# Pill_Minder_shield.net
KiCad netlist of a schematic drawn in EAGLE
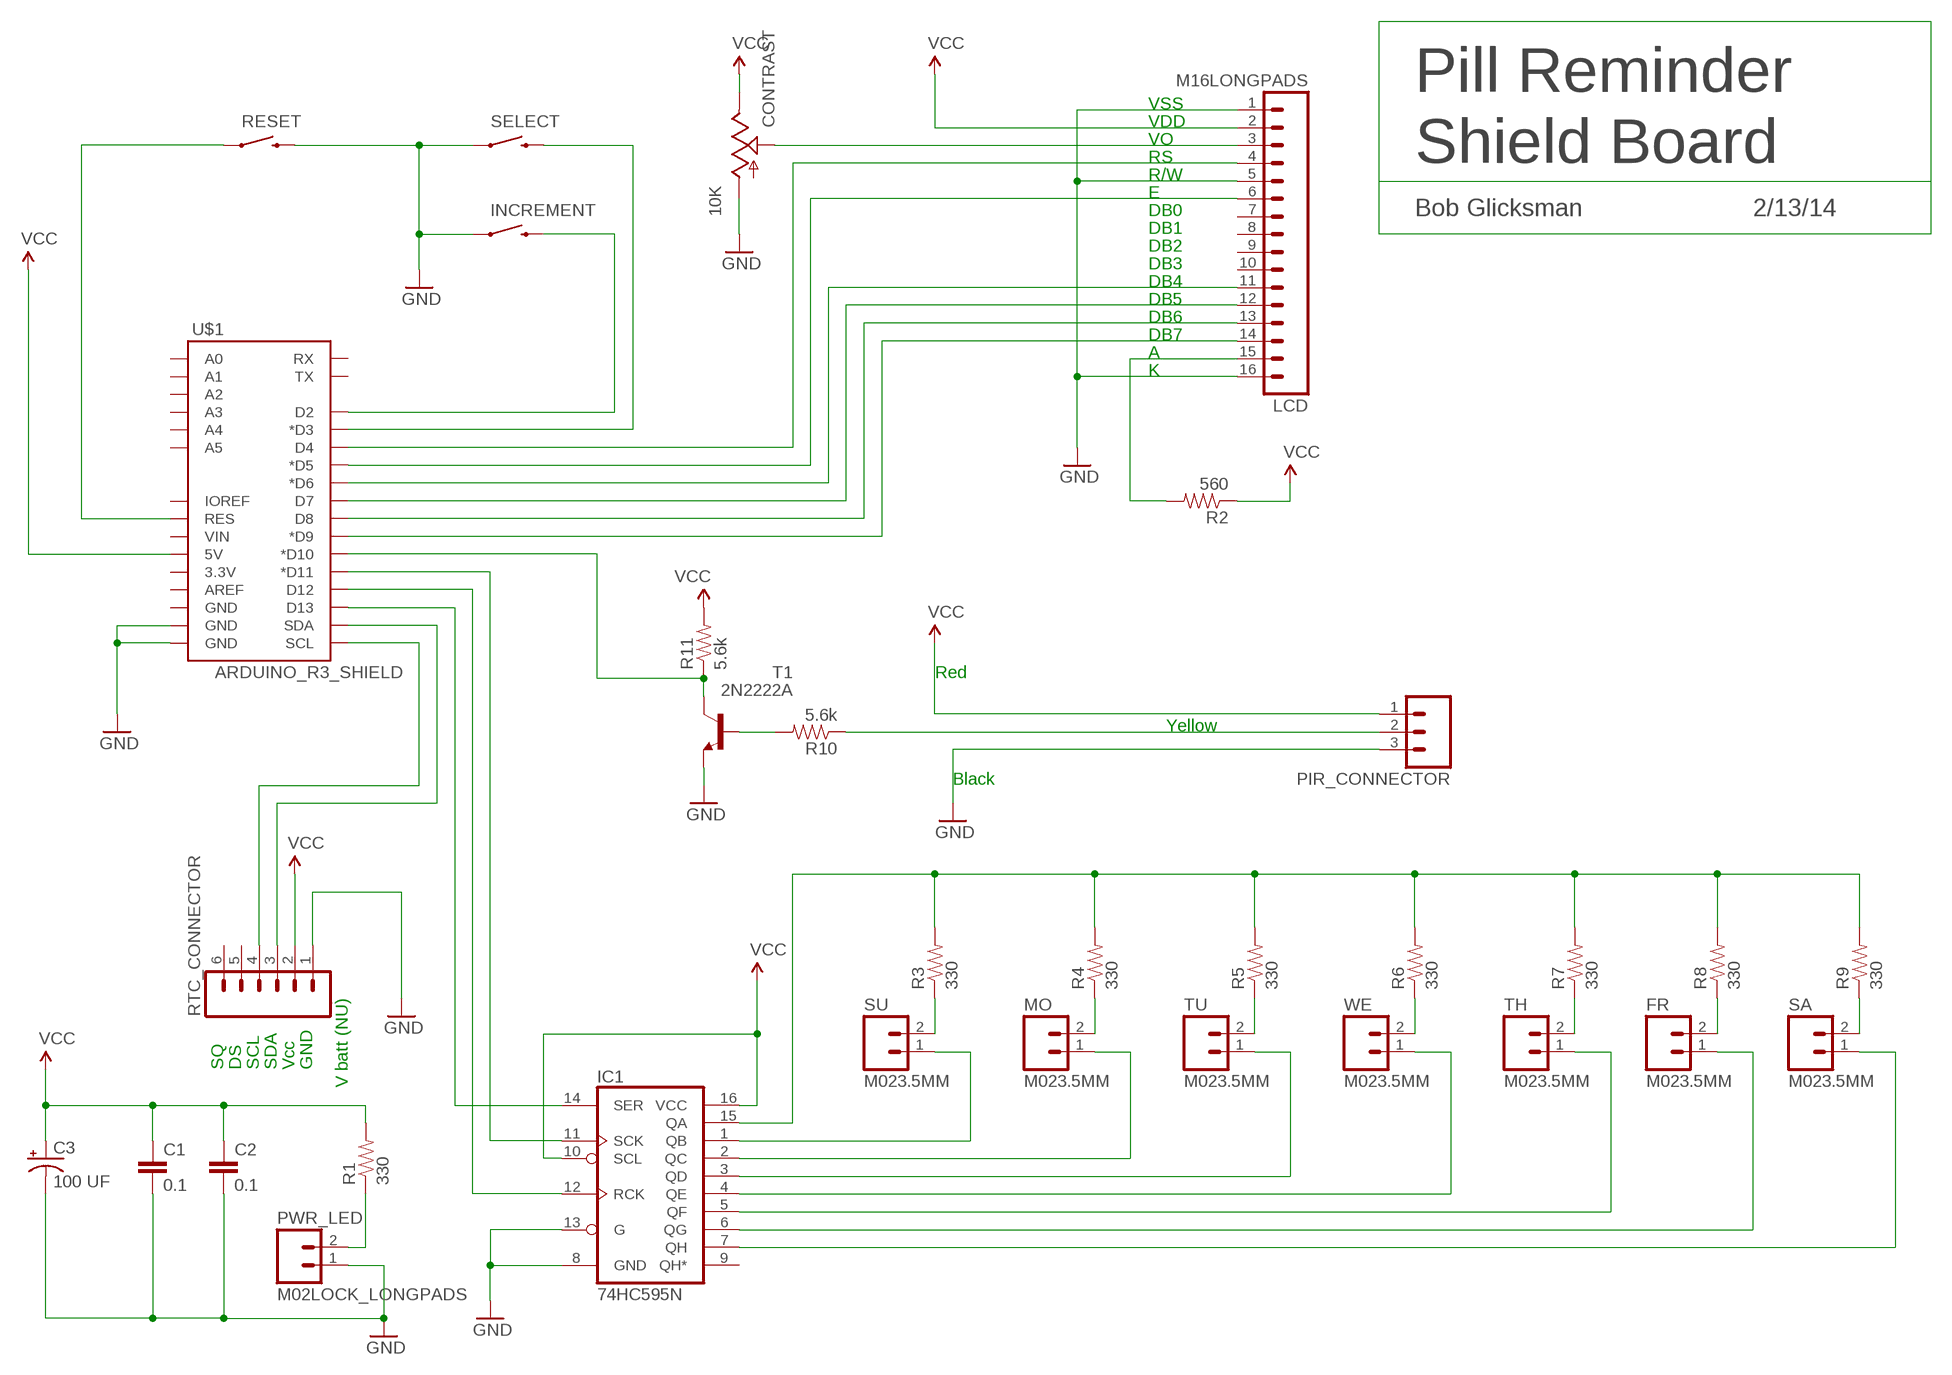
[diagram p0: schematic, sheet 1]

(export (version "E")
  (design (tool "Eeschema 10.0.6"))
  (components
    (comp (ref "C1")
      (value "0.1")
      (footprint "eagle-import:CAP-PTH-SMALL2")
      (libsource (lib "eagle-import") (part "CAPPTH2"))
    )
    (comp (ref "C2")
      (value "0.1")
      (footprint "eagle-import:CAP-PTH-SMALL2")
      (libsource (lib "eagle-import") (part "CAPPTH2"))
    )
    (comp (ref "C3")
      (value "100 UF")
      (footprint "eagle-import:CPOL-RADIAL-100UF-25V")
      (libsource (lib "eagle-import") (part "CAP_POLPTH1"))
    )
    (comp (ref "CONTRAST")
      (value "10K")
      (footprint "eagle-import:TRIM_POT")
      (libsource (lib "eagle-import") (part "POTTRIM"))
    )
    (comp (ref "FR")
      (value "M023.5MM")
      (footprint "eagle-import:SCREWTERMINAL-3.5MM-2")
      (libsource (lib "eagle-import") (part "M023.5MM"))
    )
    (comp (ref "IC1")
      (value "74HC595N")
      (footprint "eagle-import:DIL16")
      (libsource (lib "eagle-import") (part "74595NLS"))
    )
    (comp (ref "INCREMENT")
      (value "SWITCH-MOMENTARY-2PTH")
      (footprint "eagle-import:TACTILE-PTH")
      (libsource (lib "eagle-import") (part "SWITCH-MOMENTARY-2PTH"))
    )
    (comp (ref "LCD")
      (value "M16LONGPADS")
      (footprint "eagle-import:1X16_LONGPADS")
      (libsource (lib "eagle-import") (part "M16LONGPADS"))
    )
    (comp (ref "MO")
      (value "M023.5MM")
      (footprint "eagle-import:SCREWTERMINAL-3.5MM-2")
      (libsource (lib "eagle-import") (part "M023.5MM"))
    )
    (comp (ref "PIR_CONNECTOR")
      (value "M03LONGPADS")
      (footprint "eagle-import:1X03_LONGPADS")
      (libsource (lib "eagle-import") (part "M03LONGPADS"))
    )
    (comp (ref "PWR_LED")
      (value "M02LOCK_LONGPADS")
      (footprint "eagle-import:1X02_LOCK_LONGPADS")
      (libsource (lib "eagle-import") (part "M02LOCK_LONGPADS"))
    )
    (comp (ref "R1")
      (value "330")
      (footprint "eagle-import:AXIAL-0.4")
      (libsource (lib "eagle-import") (part "RESISTORPTH-1/4W"))
    )
    (comp (ref "R2")
      (value "560")
      (footprint "eagle-import:AXIAL-0.4")
      (libsource (lib "eagle-import") (part "RESISTORPTH-1/4W"))
    )
    (comp (ref "R3")
      (value "330")
      (footprint "eagle-import:AXIAL-0.4")
      (libsource (lib "eagle-import") (part "RESISTORPTH-1/4W"))
    )
    (comp (ref "R4")
      (value "330")
      (footprint "eagle-import:AXIAL-0.4")
      (libsource (lib "eagle-import") (part "RESISTORPTH-1/4W"))
    )
    (comp (ref "R5")
      (value "330")
      (footprint "eagle-import:AXIAL-0.4")
      (libsource (lib "eagle-import") (part "RESISTORPTH-1/4W"))
    )
    (comp (ref "R6")
      (value "330")
      (footprint "eagle-import:AXIAL-0.4")
      (libsource (lib "eagle-import") (part "RESISTORPTH-1/4W"))
    )
    (comp (ref "R7")
      (value "330")
      (footprint "eagle-import:AXIAL-0.4")
      (libsource (lib "eagle-import") (part "RESISTORPTH-1/4W"))
    )
    (comp (ref "R8")
      (value "330")
      (footprint "eagle-import:AXIAL-0.4")
      (libsource (lib "eagle-import") (part "RESISTORPTH-1/4W"))
    )
    (comp (ref "R9")
      (value "330")
      (footprint "eagle-import:AXIAL-0.4")
      (libsource (lib "eagle-import") (part "RESISTORPTH-1/4W"))
    )
    (comp (ref "R10")
      (value "5.6k")
      (footprint "eagle-import:AXIAL-0.4")
      (libsource (lib "eagle-import") (part "RESISTORPTH-1/4W"))
    )
    (comp (ref "R11")
      (value "5.6k")
      (footprint "eagle-import:AXIAL-0.4")
      (libsource (lib "eagle-import") (part "RESISTORPTH-1/4W"))
    )
    (comp (ref "RESET")
      (value "SWITCH-MOMENTARY-2PTH")
      (footprint "eagle-import:TACTILE-PTH")
      (libsource (lib "eagle-import") (part "SWITCH-MOMENTARY-2PTH"))
    )
    (comp (ref "RTC_CONNECTOR")
      (value "M06LONGPADS")
      (footprint "eagle-import:1X06_LONGPADS")
      (libsource (lib "eagle-import") (part "M06LONGPADS"))
    )
    (comp (ref "SA")
      (value "M023.5MM")
      (footprint "eagle-import:SCREWTERMINAL-3.5MM-2")
      (libsource (lib "eagle-import") (part "M023.5MM"))
    )
    (comp (ref "SELECT")
      (value "SWITCH-MOMENTARY-2PTH")
      (footprint "eagle-import:TACTILE-PTH")
      (libsource (lib "eagle-import") (part "SWITCH-MOMENTARY-2PTH"))
    )
    (comp (ref "SU")
      (value "M023.5MM")
      (footprint "eagle-import:SCREWTERMINAL-3.5MM-2")
      (libsource (lib "eagle-import") (part "M023.5MM"))
    )
    (comp (ref "T1")
      (value "2N2222A")
      (footprint "eagle-import:TO92-EBC")
      (libsource (lib "eagle-import") (part "-NPN-TO92-EBC"))
    )
    (comp (ref "TH")
      (value "M023.5MM")
      (footprint "eagle-import:SCREWTERMINAL-3.5MM-2")
      (libsource (lib "eagle-import") (part "M023.5MM"))
    )
    (comp (ref "TU")
      (value "M023.5MM")
      (footprint "eagle-import:SCREWTERMINAL-3.5MM-2")
      (libsource (lib "eagle-import") (part "M023.5MM"))
    )
    (comp (ref "U$1")
      (value "ARDUINO_R3_SHIELD")
      (footprint "eagle-import:UNO_R3_SHIELD")
      (libsource (lib "eagle-import") (part "ARDUINO_R3_SHIELD"))
    )
    (comp (ref "WE")
      (value "M023.5MM")
      (footprint "eagle-import:SCREWTERMINAL-3.5MM-2")
      (libsource (lib "eagle-import") (part "M023.5MM"))
    )
  )
  (nets
    (net (code "1") (name "GND") (class "Default")
      (node (ref "C1") (pin "2") (pinfunction "2_2") (pintype "passive"))
      (node (ref "C2") (pin "2") (pinfunction "2_2") (pintype "passive"))
      (node (ref "C3") (pin "2") (pinfunction "-_2") (pintype "passive"))
      (node (ref "CONTRAST") (pin "3") (pinfunction "A_3") (pintype "passive"))
      (node (ref "IC1") (pin "13") (pinfunction "G_13") (pintype "input"))
      (node (ref "IC1") (pin "8") (pinfunction "GND_8") (pintype "power_in"))
      (node (ref "INCREMENT") (pin "1") (pinfunction "1_1") (pintype "passive"))
      (node (ref "LCD") (pin "1") (pinfunction "1_1") (pintype "passive"))
      (node (ref "LCD") (pin "16") (pinfunction "16_16") (pintype "passive"))
      (node (ref "LCD") (pin "5") (pinfunction "5_5") (pintype "passive"))
      (node (ref "PIR_CONNECTOR") (pin "3") (pinfunction "3_3") (pintype "passive"))
      (node (ref "PWR_LED") (pin "1") (pinfunction "1_1") (pintype "passive"))
      (node (ref "RESET") (pin "3") (pinfunction "2_3") (pintype "passive"))
      (node (ref "RTC_CONNECTOR") (pin "1") (pinfunction "1_1") (pintype "passive"))
      (node (ref "SELECT") (pin "1") (pinfunction "1_1") (pintype "passive"))
      (node (ref "T1") (pin "E") (pinfunction "E_E") (pintype "passive"))
      (node (ref "U$1") (pin "GND@0") (pinfunction "GND_GND@0") (pintype "bidirectional"))
      (node (ref "U$1") (pin "GND@1") (pinfunction "GND_GND@1") (pintype "bidirectional"))
    )
    (net (code "2") (name "Net-(CONTRAST-S)") (class "Default")
      (node (ref "CONTRAST") (pin "1") (pinfunction "S_1") (pintype "passive"))
      (node (ref "LCD") (pin "3") (pinfunction "3_3") (pintype "passive"))
    )
    (net (code "3") (name "Net-(IC1-QA)") (class "Default")
      (node (ref "IC1") (pin "15") (pinfunction "QA_15") (pintype "tri_state"))
      (node (ref "R3") (pin "P$2") (pinfunction "2_P$2") (pintype "passive"))
      (node (ref "R4") (pin "P$2") (pinfunction "2_P$2") (pintype "passive"))
      (node (ref "R5") (pin "P$2") (pinfunction "2_P$2") (pintype "passive"))
      (node (ref "R6") (pin "P$2") (pinfunction "2_P$2") (pintype "passive"))
      (node (ref "R7") (pin "P$2") (pinfunction "2_P$2") (pintype "passive"))
      (node (ref "R8") (pin "P$2") (pinfunction "2_P$2") (pintype "passive"))
      (node (ref "R9") (pin "P$2") (pinfunction "2_P$2") (pintype "passive"))
    )
    (net (code "4") (name "Net-(IC1-QB)") (class "Default")
      (node (ref "IC1") (pin "1") (pinfunction "QB_1") (pintype "tri_state"))
      (node (ref "SU") (pin "1") (pinfunction "1_1") (pintype "passive"))
    )
    (net (code "5") (name "Net-(IC1-QC)") (class "Default")
      (node (ref "IC1") (pin "2") (pinfunction "QC_2") (pintype "tri_state"))
      (node (ref "MO") (pin "1") (pinfunction "1_1") (pintype "passive"))
    )
    (net (code "6") (name "Net-(IC1-QD)") (class "Default")
      (node (ref "IC1") (pin "3") (pinfunction "QD_3") (pintype "tri_state"))
      (node (ref "TU") (pin "1") (pinfunction "1_1") (pintype "passive"))
    )
    (net (code "7") (name "Net-(IC1-QE)") (class "Default")
      (node (ref "IC1") (pin "4") (pinfunction "QE_4") (pintype "tri_state"))
      (node (ref "WE") (pin "1") (pinfunction "1_1") (pintype "passive"))
    )
    (net (code "8") (name "Net-(IC1-QF)") (class "Default")
      (node (ref "IC1") (pin "5") (pinfunction "QF_5") (pintype "tri_state"))
      (node (ref "TH") (pin "1") (pinfunction "1_1") (pintype "passive"))
    )
    (net (code "9") (name "Net-(IC1-QG)") (class "Default")
      (node (ref "FR") (pin "1") (pinfunction "1_1") (pintype "passive"))
      (node (ref "IC1") (pin "6") (pinfunction "QG_6") (pintype "tri_state"))
    )
    (net (code "10") (name "Net-(IC1-QH)") (class "Default")
      (node (ref "IC1") (pin "7") (pinfunction "QH_7") (pintype "tri_state"))
      (node (ref "SA") (pin "1") (pinfunction "1_1") (pintype "passive"))
    )
    (net (code "11") (name "Net-(IC1-RCK)") (class "Default")
      (node (ref "IC1") (pin "12") (pinfunction "RCK_12") (pintype "input"))
      (node (ref "U$1") (pin "D12") (pinfunction "D12_D12") (pintype "bidirectional"))
    )
    (net (code "12") (name "Net-(IC1-SCK)") (class "Default")
      (node (ref "IC1") (pin "11") (pinfunction "SCK_11") (pintype "input"))
      (node (ref "U$1") (pin "D11") (pinfunction "*D11_D11") (pintype "bidirectional"))
    )
    (net (code "13") (name "Net-(IC1-SER)") (class "Default")
      (node (ref "IC1") (pin "14") (pinfunction "SER_14") (pintype "input"))
      (node (ref "U$1") (pin "D13") (pinfunction "D13_D13") (pintype "bidirectional"))
    )
    (net (code "14") (name "Net-(INCREMENT-2)") (class "Default")
      (node (ref "INCREMENT") (pin "3") (pinfunction "2_3") (pintype "passive"))
      (node (ref "U$1") (pin "D2") (pinfunction "D2_D2") (pintype "bidirectional"))
    )
    (net (code "15") (name "Net-(LCD-Pad4)") (class "Default")
      (node (ref "LCD") (pin "4") (pinfunction "4_4") (pintype "passive"))
      (node (ref "U$1") (pin "D4") (pinfunction "D4_D4") (pintype "bidirectional"))
    )
    (net (code "16") (name "Net-(LCD-Pad12)") (class "Default")
      (node (ref "LCD") (pin "12") (pinfunction "12_12") (pintype "passive"))
      (node (ref "U$1") (pin "D7") (pinfunction "D7_D7") (pintype "bidirectional"))
    )
    (net (code "17") (name "Net-(LCD-Pad13)") (class "Default")
      (node (ref "LCD") (pin "13") (pinfunction "13_13") (pintype "passive"))
      (node (ref "U$1") (pin "D8") (pinfunction "D8_D8") (pintype "bidirectional"))
    )
    (net (code "18") (name "Net-(R1-1)") (class "Default")
      (node (ref "PWR_LED") (pin "2") (pinfunction "2_2") (pintype "passive"))
      (node (ref "R1") (pin "P$1") (pinfunction "1_P$1") (pintype "passive"))
    )
    (net (code "19") (name "Net-(R2-2)") (class "Default")
      (node (ref "LCD") (pin "15") (pinfunction "15_15") (pintype "passive"))
      (node (ref "R2") (pin "P$2") (pinfunction "2_P$2") (pintype "passive"))
    )
    (net (code "20") (name "Net-(R3-1)") (class "Default")
      (node (ref "R3") (pin "P$1") (pinfunction "1_P$1") (pintype "passive"))
      (node (ref "SU") (pin "2") (pinfunction "2_2") (pintype "passive"))
    )
    (net (code "21") (name "Net-(R4-1)") (class "Default")
      (node (ref "MO") (pin "2") (pinfunction "2_2") (pintype "passive"))
      (node (ref "R4") (pin "P$1") (pinfunction "1_P$1") (pintype "passive"))
    )
    (net (code "22") (name "Net-(R5-1)") (class "Default")
      (node (ref "R5") (pin "P$1") (pinfunction "1_P$1") (pintype "passive"))
      (node (ref "TU") (pin "2") (pinfunction "2_2") (pintype "passive"))
    )
    (net (code "23") (name "Net-(R6-1)") (class "Default")
      (node (ref "R6") (pin "P$1") (pinfunction "1_P$1") (pintype "passive"))
      (node (ref "WE") (pin "2") (pinfunction "2_2") (pintype "passive"))
    )
    (net (code "24") (name "Net-(R7-1)") (class "Default")
      (node (ref "R7") (pin "P$1") (pinfunction "1_P$1") (pintype "passive"))
      (node (ref "TH") (pin "2") (pinfunction "2_2") (pintype "passive"))
    )
    (net (code "25") (name "Net-(R8-1)") (class "Default")
      (node (ref "FR") (pin "2") (pinfunction "2_2") (pintype "passive"))
      (node (ref "R8") (pin "P$1") (pinfunction "1_P$1") (pintype "passive"))
    )
    (net (code "26") (name "Net-(R9-1)") (class "Default")
      (node (ref "R9") (pin "P$1") (pinfunction "1_P$1") (pintype "passive"))
      (node (ref "SA") (pin "2") (pinfunction "2_2") (pintype "passive"))
    )
    (net (code "27") (name "Net-(R10-1)") (class "Default")
      (node (ref "PIR_CONNECTOR") (pin "2") (pinfunction "2_2") (pintype "passive"))
      (node (ref "R10") (pin "P$1") (pinfunction "1_P$1") (pintype "passive"))
    )
    (net (code "28") (name "Net-(R10-2)") (class "Default")
      (node (ref "R10") (pin "P$2") (pinfunction "2_P$2") (pintype "passive"))
      (node (ref "T1") (pin "B") (pinfunction "B_B") (pintype "passive"))
    )
    (net (code "29") (name "Net-(R11-1)") (class "Default")
      (node (ref "R11") (pin "P$1") (pinfunction "1_P$1") (pintype "passive"))
      (node (ref "T1") (pin "C") (pinfunction "C_C") (pintype "passive"))
      (node (ref "U$1") (pin "D10") (pinfunction "*D10_D10") (pintype "bidirectional"))
    )
    (net (code "30") (name "Net-(RESET-Pad1)") (class "Default")
      (node (ref "RESET") (pin "1") (pinfunction "1_1") (pintype "passive"))
      (node (ref "U$1") (pin "RES") (pinfunction "RES_RES") (pintype "bidirectional"))
    )
    (net (code "31") (name "Net-(RTC_CONNECTOR-Pad3)") (class "Default")
      (node (ref "RTC_CONNECTOR") (pin "3") (pinfunction "3_3") (pintype "passive"))
      (node (ref "U$1") (pin "SDA") (pinfunction "SDA_SDA") (pintype "bidirectional"))
    )
    (net (code "32") (name "Net-(RTC_CONNECTOR-Pad4)") (class "Default")
      (node (ref "RTC_CONNECTOR") (pin "4") (pinfunction "4_4") (pintype "passive"))
      (node (ref "U$1") (pin "SCL") (pinfunction "SCL_SCL") (pintype "bidirectional"))
    )
    (net (code "33") (name "Net-(SELECT-2)") (class "Default")
      (node (ref "SELECT") (pin "3") (pinfunction "2_3") (pintype "passive"))
      (node (ref "U$1") (pin "D3") (pinfunction "*D3_D3") (pintype "bidirectional"))
    )
    (net (code "34") (name "Net-(U$1-*D5)") (class "Default")
      (node (ref "LCD") (pin "6") (pinfunction "6_6") (pintype "passive"))
      (node (ref "U$1") (pin "D5") (pinfunction "*D5_D5") (pintype "bidirectional"))
    )
    (net (code "35") (name "Net-(U$1-*D6)") (class "Default")
      (node (ref "LCD") (pin "11") (pinfunction "11_11") (pintype "passive"))
      (node (ref "U$1") (pin "D6") (pinfunction "*D6_D6") (pintype "bidirectional"))
    )
    (net (code "36") (name "Net-(U$1-*D9)") (class "Default")
      (node (ref "LCD") (pin "14") (pinfunction "14_14") (pintype "passive"))
      (node (ref "U$1") (pin "D9") (pinfunction "*D9_D9") (pintype "bidirectional"))
    )
    (net (code "37") (name "VCC") (class "Default")
      (node (ref "C1") (pin "1") (pinfunction "1_1") (pintype "passive"))
      (node (ref "C2") (pin "1") (pinfunction "1_1") (pintype "passive"))
      (node (ref "C3") (pin "1") (pinfunction "+_1") (pintype "passive"))
      (node (ref "CONTRAST") (pin "2") (pinfunction "E_2") (pintype "passive"))
      (node (ref "IC1") (pin "10") (pinfunction "SCL_10") (pintype "input"))
      (node (ref "IC1") (pin "16") (pinfunction "VCC_16") (pintype "power_in"))
      (node (ref "LCD") (pin "2") (pinfunction "2_2") (pintype "passive"))
      (node (ref "PIR_CONNECTOR") (pin "1") (pinfunction "1_1") (pintype "passive"))
      (node (ref "R1") (pin "P$2") (pinfunction "2_P$2") (pintype "passive"))
      (node (ref "R11") (pin "P$2") (pinfunction "2_P$2") (pintype "passive"))
      (node (ref "R2") (pin "P$1") (pinfunction "1_P$1") (pintype "passive"))
      (node (ref "RTC_CONNECTOR") (pin "2") (pinfunction "2_2") (pintype "passive"))
      (node (ref "U$1") (pin "5V") (pinfunction "5V_5V") (pintype "bidirectional"))
    )
    (net (code "38") (name "unconnected-(IC1-QH*-Pad9)") (class "Default")
      (node (ref "IC1") (pin "9") (pinfunction "QH*_9") (pintype "tri_state"))
    )
    (net (code "39") (name "unconnected-(LCD-Pad7)") (class "Default")
      (node (ref "LCD") (pin "7") (pinfunction "7_7") (pintype "passive"))
    )
    (net (code "40") (name "unconnected-(LCD-Pad8)") (class "Default")
      (node (ref "LCD") (pin "8") (pinfunction "8_8") (pintype "passive"))
    )
    (net (code "41") (name "unconnected-(LCD-Pad9)") (class "Default")
      (node (ref "LCD") (pin "9") (pinfunction "9_9") (pintype "passive"))
    )
    (net (code "42") (name "unconnected-(LCD-Pad10)") (class "Default")
      (node (ref "LCD") (pin "10") (pinfunction "10_10") (pintype "passive"))
    )
    (net (code "43") (name "unconnected-(RTC_CONNECTOR-Pad5)") (class "Default")
      (node (ref "RTC_CONNECTOR") (pin "5") (pinfunction "5_5") (pintype "passive"))
    )
    (net (code "44") (name "unconnected-(RTC_CONNECTOR-Pad6)") (class "Default")
      (node (ref "RTC_CONNECTOR") (pin "6") (pinfunction "6_6") (pintype "passive"))
    )
    (net (code "45") (name "unconnected-(U$1-GND-PadGND@2)") (class "Default")
      (node (ref "U$1") (pin "GND@2") (pinfunction "GND_GND@2") (pintype "bidirectional"))
    )
    (net (code "46") (name "unconnected-(U$1-Pad3.3V)") (class "Default")
      (node (ref "U$1") (pin "3.3V") (pinfunction "3.3V_3.3V") (pintype "bidirectional"))
    )
    (net (code "47") (name "unconnected-(U$1-PadA0)") (class "Default")
      (node (ref "U$1") (pin "A0") (pinfunction "A0_A0") (pintype "bidirectional"))
    )
    (net (code "48") (name "unconnected-(U$1-PadA1)") (class "Default")
      (node (ref "U$1") (pin "A1") (pinfunction "A1_A1") (pintype "bidirectional"))
    )
    (net (code "49") (name "unconnected-(U$1-PadA2)") (class "Default")
      (node (ref "U$1") (pin "A2") (pinfunction "A2_A2") (pintype "bidirectional"))
    )
    (net (code "50") (name "unconnected-(U$1-PadA3)") (class "Default")
      (node (ref "U$1") (pin "A3") (pinfunction "A3_A3") (pintype "bidirectional"))
    )
    (net (code "51") (name "unconnected-(U$1-PadA4)") (class "Default")
      (node (ref "U$1") (pin "A4") (pinfunction "A4_A4") (pintype "bidirectional"))
    )
    (net (code "52") (name "unconnected-(U$1-PadA5)") (class "Default")
      (node (ref "U$1") (pin "A5") (pinfunction "A5_A5") (pintype "bidirectional"))
    )
    (net (code "53") (name "unconnected-(U$1-PadAREF)") (class "Default")
      (node (ref "U$1") (pin "AREF") (pinfunction "AREF_AREF") (pintype "bidirectional"))
    )
    (net (code "54") (name "unconnected-(U$1-PadIOREF)") (class "Default")
      (node (ref "U$1") (pin "IOREF") (pinfunction "IOREF_IOREF") (pintype "bidirectional"))
    )
    (net (code "55") (name "unconnected-(U$1-PadRX)") (class "Default")
      (node (ref "U$1") (pin "RX") (pinfunction "RX_RX") (pintype "bidirectional"))
    )
    (net (code "56") (name "unconnected-(U$1-PadTX)") (class "Default")
      (node (ref "U$1") (pin "TX") (pinfunction "TX_TX") (pintype "bidirectional"))
    )
    (net (code "57") (name "unconnected-(U$1-PadVIN)") (class "Default")
      (node (ref "U$1") (pin "VIN") (pinfunction "VIN_VIN") (pintype "bidirectional"))
    )
  )
)
